# MainBoard.net
KiCad netlist of a schematic drawn in EAGLE
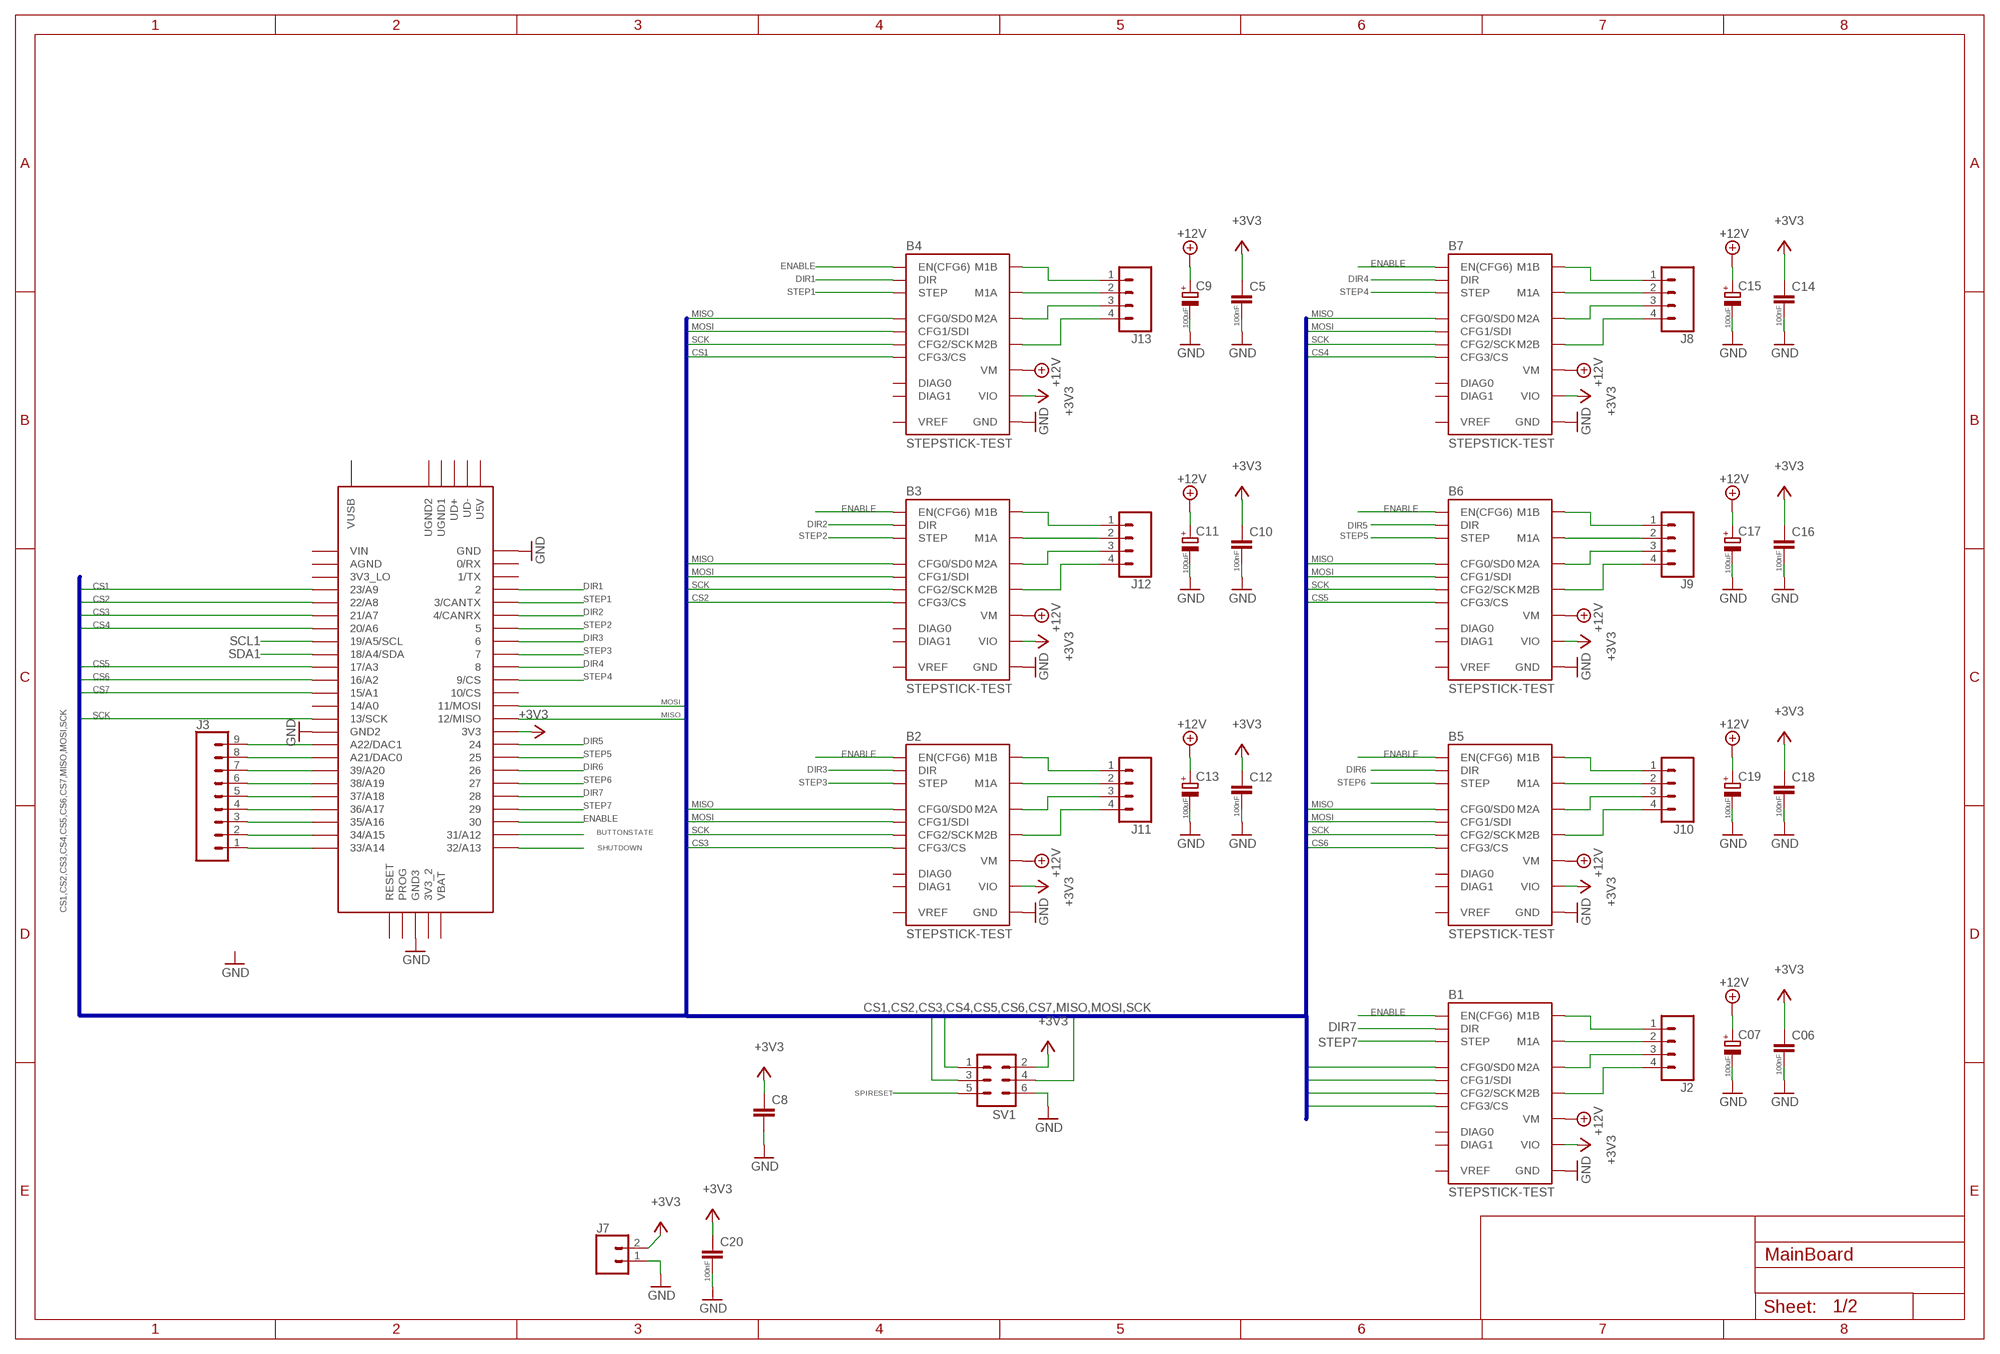
[diagram p0: schematic, sheet 1]
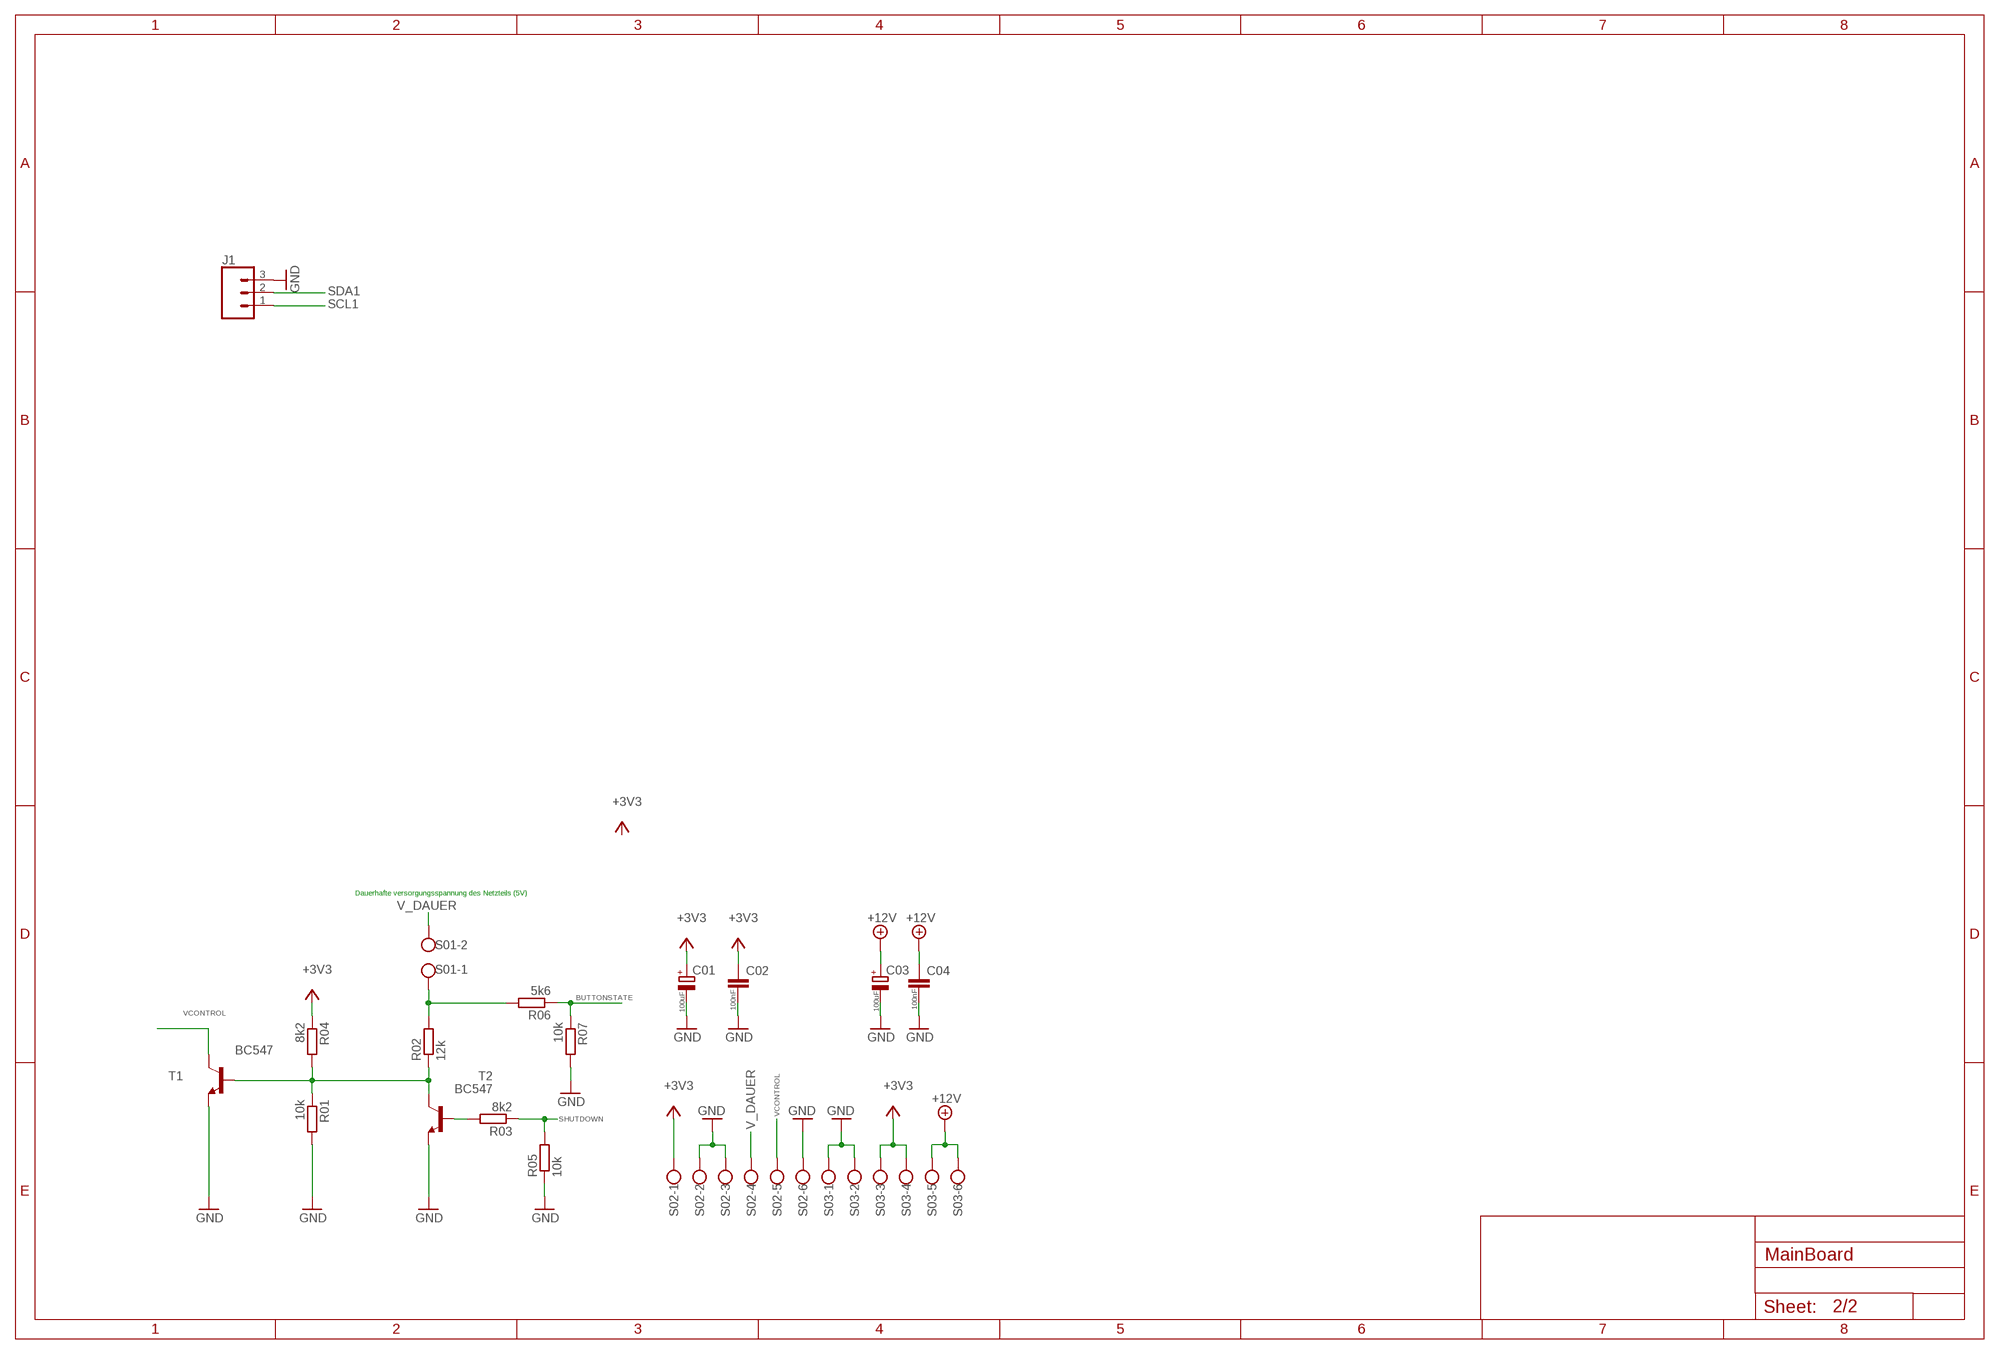
[diagram p1: schematic, sheet 2]

(export (version "E")
  (design (tool "Eeschema 10.0.6"))
  (components
    (comp (ref "C01")
      (value "100uF")
      (footprint "eagle-import:E2,5-6")
      (libsource (lib "eagle-import") (part "CPOL-EUE2.5-6"))
    )
    (comp (ref "C02")
      (value "100nF")
      (footprint "eagle-import:C050-024X044")
      (libsource (lib "eagle-import") (part "C-EU050-024X044"))
    )
    (comp (ref "C03")
      (value "100uF")
      (footprint "eagle-import:E2,5-6")
      (libsource (lib "eagle-import") (part "CPOL-EUE2.5-6"))
    )
    (comp (ref "C04")
      (value "100nF")
      (footprint "eagle-import:C050-024X044")
      (libsource (lib "eagle-import") (part "C-EU050-024X044"))
    )
    (comp (ref "J1")
      (value "CONN_03LONGPADS")
      (footprint "eagle-import:1X03_LONGPADS")
      (libsource (lib "eagle-import") (part "CONN_03LONGPADS"))
    )
    (comp (ref "R01")
      (value "10k")
      (footprint "eagle-import:0207_10")
      (libsource (lib "eagle-import") (part "R-EU_0207/10"))
    )
    (comp (ref "R02")
      (value "12k")
      (footprint "eagle-import:0207_10")
      (libsource (lib "eagle-import") (part "R-EU_0207/10"))
    )
    (comp (ref "R03")
      (value "8k2")
      (footprint "eagle-import:0207_10")
      (libsource (lib "eagle-import") (part "R-EU_0207/10"))
    )
    (comp (ref "R04")
      (value "8k2")
      (footprint "eagle-import:0207_10")
      (libsource (lib "eagle-import") (part "R-EU_0207/10"))
    )
    (comp (ref "R05")
      (value "10k")
      (footprint "eagle-import:0207_10")
      (libsource (lib "eagle-import") (part "R-EU_0207/10"))
    )
    (comp (ref "R06")
      (value "5k6")
      (footprint "eagle-import:0207_10")
      (libsource (lib "eagle-import") (part "R-EU_0207/10"))
    )
    (comp (ref "R07")
      (value "10k")
      (footprint "eagle-import:0207_10")
      (libsource (lib "eagle-import") (part "R-EU_0207/10"))
    )
    (comp (ref "S01")
      (value "W237-102")
      (footprint "eagle-import:W237-102")
      (fields (field (name "MPN") "237-102"))
      (libsource (lib "eagle-import") (part "W237-102"))
    )
    (comp (ref "S02")
      (value "W237-6")
      (footprint "eagle-import:W237-6")
      (libsource (lib "eagle-import") (part "W237-6"))
    )
    (comp (ref "S03")
      (value "W237-6")
      (footprint "eagle-import:W237-6")
      (libsource (lib "eagle-import") (part "W237-6"))
    )
    (comp (ref "T1")
      (value "BC547")
      (footprint "eagle-import:TO92")
      (libsource (lib "eagle-import") (part "BC547"))
    )
    (comp (ref "T2")
      (value "BC547")
      (footprint "eagle-import:TO92")
      (libsource (lib "eagle-import") (part "BC547"))
    )
    (comp (ref "B1")
      (value "STEPSTICK-TEST")
      (footprint "eagle-import:STEPSTICK-TEST")
      (libsource (lib "eagle-import") (part "STEPSTICK-TEST"))
    )
    (comp (ref "B2")
      (value "STEPSTICK-TEST")
      (footprint "eagle-import:STEPSTICK-TEST")
      (libsource (lib "eagle-import") (part "STEPSTICK-TEST"))
    )
    (comp (ref "B3")
      (value "STEPSTICK-TEST")
      (footprint "eagle-import:STEPSTICK-TEST")
      (libsource (lib "eagle-import") (part "STEPSTICK-TEST"))
    )
    (comp (ref "B4")
      (value "STEPSTICK-TEST")
      (footprint "eagle-import:STEPSTICK-TEST")
      (libsource (lib "eagle-import") (part "STEPSTICK-TEST"))
    )
    (comp (ref "B5")
      (value "STEPSTICK-TEST")
      (footprint "eagle-import:STEPSTICK-TEST")
      (libsource (lib "eagle-import") (part "STEPSTICK-TEST"))
    )
    (comp (ref "B6")
      (value "STEPSTICK-TEST")
      (footprint "eagle-import:STEPSTICK-TEST")
      (libsource (lib "eagle-import") (part "STEPSTICK-TEST"))
    )
    (comp (ref "B7")
      (value "STEPSTICK-TEST")
      (footprint "eagle-import:STEPSTICK-TEST")
      (libsource (lib "eagle-import") (part "STEPSTICK-TEST"))
    )
    (comp (ref "C5")
      (value "100nF")
      (footprint "eagle-import:C050-024X044")
      (libsource (lib "eagle-import") (part "C-EU050-024X044"))
    )
    (comp (ref "C06")
      (value "100nF")
      (footprint "eagle-import:C050-024X044")
      (libsource (lib "eagle-import") (part "C-EU050-024X044"))
    )
    (comp (ref "C07")
      (value "100uF")
      (footprint "eagle-import:E2,5-6")
      (libsource (lib "eagle-import") (part "CPOL-EUE2.5-6"))
    )
    (comp (ref "C8")
      (value "C-EU050-024X044")
      (footprint "eagle-import:C050-024X044")
      (libsource (lib "eagle-import") (part "C-EU050-024X044"))
    )
    (comp (ref "C9")
      (value "100uF")
      (footprint "eagle-import:E2,5-6")
      (libsource (lib "eagle-import") (part "CPOL-EUE2.5-6"))
    )
    (comp (ref "C10")
      (value "100nF")
      (footprint "eagle-import:C050-024X044")
      (libsource (lib "eagle-import") (part "C-EU050-024X044"))
    )
    (comp (ref "C11")
      (value "100uF")
      (footprint "eagle-import:E2,5-6")
      (libsource (lib "eagle-import") (part "CPOL-EUE2.5-6"))
    )
    (comp (ref "C12")
      (value "100nF")
      (footprint "eagle-import:C050-024X044")
      (libsource (lib "eagle-import") (part "C-EU050-024X044"))
    )
    (comp (ref "C13")
      (value "100uF")
      (footprint "eagle-import:E2,5-6")
      (libsource (lib "eagle-import") (part "CPOL-EUE2.5-6"))
    )
    (comp (ref "C14")
      (value "100nF")
      (footprint "eagle-import:C050-024X044")
      (libsource (lib "eagle-import") (part "C-EU050-024X044"))
    )
    (comp (ref "C15")
      (value "100uF")
      (footprint "eagle-import:E2,5-6")
      (libsource (lib "eagle-import") (part "CPOL-EUE2.5-6"))
    )
    (comp (ref "C16")
      (value "100nF")
      (footprint "eagle-import:C050-024X044")
      (libsource (lib "eagle-import") (part "C-EU050-024X044"))
    )
    (comp (ref "C17")
      (value "100uF")
      (footprint "eagle-import:E2,5-6")
      (libsource (lib "eagle-import") (part "CPOL-EUE2.5-6"))
    )
    (comp (ref "C18")
      (value "100nF")
      (footprint "eagle-import:C050-024X044")
      (libsource (lib "eagle-import") (part "C-EU050-024X044"))
    )
    (comp (ref "C19")
      (value "100uF")
      (footprint "eagle-import:E2,5-6")
      (libsource (lib "eagle-import") (part "CPOL-EUE2.5-6"))
    )
    (comp (ref "C20")
      (value "100nF")
      (footprint "eagle-import:C050-024X044")
      (libsource (lib "eagle-import") (part "C-EU050-024X044"))
    )
    (comp (ref "J2")
      (value "CONN_041X04_NO_SILK")
      (footprint "eagle-import:1X04_NO_SILK")
      (libsource (lib "eagle-import") (part "CONN_041X04_NO_SILK"))
    )
    (comp (ref "J3")
      (value "CONN_09LONGPADS")
      (footprint "eagle-import:1X09_LONGPADS")
      (libsource (lib "eagle-import") (part "CONN_09LONGPADS"))
    )
    (comp (ref "J7")
      (value "CONN_02PTH3")
      (footprint "eagle-import:1X02_LONGPADS")
      (libsource (lib "eagle-import") (part "CONN_02PTH3"))
    )
    (comp (ref "J8")
      (value "CONN_041X04_NO_SILK")
      (footprint "eagle-import:1X04_NO_SILK")
      (libsource (lib "eagle-import") (part "CONN_041X04_NO_SILK"))
    )
    (comp (ref "J9")
      (value "CONN_041X04_NO_SILK")
      (footprint "eagle-import:1X04_NO_SILK")
      (libsource (lib "eagle-import") (part "CONN_041X04_NO_SILK"))
    )
    (comp (ref "J10")
      (value "CONN_041X04_NO_SILK")
      (footprint "eagle-import:1X04_NO_SILK")
      (libsource (lib "eagle-import") (part "CONN_041X04_NO_SILK"))
    )
    (comp (ref "J11")
      (value "CONN_041X04_NO_SILK")
      (footprint "eagle-import:1X04_NO_SILK")
      (libsource (lib "eagle-import") (part "CONN_041X04_NO_SILK"))
    )
    (comp (ref "J12")
      (value "CONN_041X04_NO_SILK")
      (footprint "eagle-import:1X04_NO_SILK")
      (libsource (lib "eagle-import") (part "CONN_041X04_NO_SILK"))
    )
    (comp (ref "J13")
      (value "CONN_041X04_NO_SILK")
      (footprint "eagle-import:1X04_NO_SILK")
      (libsource (lib "eagle-import") (part "CONN_041X04_NO_SILK"))
    )
    (comp (ref "SV1")
      (value "MA03-2")
      (footprint "eagle-import:MA03-2")
      (libsource (lib "eagle-import") (part "MA03-2"))
    )
    (comp (ref "U$1")
      (value "TEENSY_4.1")
      (footprint "eagle-import:TEENSY_4.1")
      (libsource (lib "eagle-import") (part "TEENSY_4.1"))
    )
  )
  (nets
    (net (code "1") (name "+3V3") (class "Default")
      (node (ref "B1") (pin "VIO") (pinfunction "VIO_VIO") (pintype "power_in"))
      (node (ref "B2") (pin "VIO") (pinfunction "VIO_VIO") (pintype "power_in"))
      (node (ref "B3") (pin "VIO") (pinfunction "VIO_VIO") (pintype "power_in"))
      (node (ref "B4") (pin "VIO") (pinfunction "VIO_VIO") (pintype "power_in"))
      (node (ref "B5") (pin "VIO") (pinfunction "VIO_VIO") (pintype "power_in"))
      (node (ref "B6") (pin "VIO") (pinfunction "VIO_VIO") (pintype "power_in"))
      (node (ref "B7") (pin "VIO") (pinfunction "VIO_VIO") (pintype "power_in"))
      (node (ref "C01") (pin "+") (pinfunction "+_+") (pintype "passive"))
      (node (ref "C02") (pin "1") (pinfunction "1_1") (pintype "passive"))
      (node (ref "C06") (pin "1") (pinfunction "1_1") (pintype "passive"))
      (node (ref "C10") (pin "1") (pinfunction "1_1") (pintype "passive"))
      (node (ref "C12") (pin "1") (pinfunction "1_1") (pintype "passive"))
      (node (ref "C14") (pin "1") (pinfunction "1_1") (pintype "passive"))
      (node (ref "C16") (pin "1") (pinfunction "1_1") (pintype "passive"))
      (node (ref "C18") (pin "1") (pinfunction "1_1") (pintype "passive"))
      (node (ref "C20") (pin "1") (pinfunction "1_1") (pintype "passive"))
      (node (ref "C5") (pin "1") (pinfunction "1_1") (pintype "passive"))
      (node (ref "C8") (pin "1") (pinfunction "1_1") (pintype "passive"))
      (node (ref "J7") (pin "2") (pinfunction "2_2") (pintype "passive"))
      (node (ref "R04") (pin "1") (pinfunction "1_1") (pintype "passive"))
      (node (ref "S02") (pin "1") (pinfunction "KL_1") (pintype "passive"))
      (node (ref "S03") (pin "3") (pinfunction "KL_3") (pintype "passive"))
      (node (ref "S03") (pin "4") (pinfunction "KL_4") (pintype "passive"))
      (node (ref "SV1") (pin "2") (pinfunction "2_2") (pintype "passive"))
      (node (ref "U$1") (pin "3V3") (pinfunction "3V3_3V3") (pintype "bidirectional"))
    )
    (net (code "2") (name "+12V") (class "Default")
      (node (ref "B1") (pin "VM") (pinfunction "VM_VM") (pintype "power_in"))
      (node (ref "B2") (pin "VM") (pinfunction "VM_VM") (pintype "power_in"))
      (node (ref "B3") (pin "VM") (pinfunction "VM_VM") (pintype "power_in"))
      (node (ref "B4") (pin "VM") (pinfunction "VM_VM") (pintype "power_in"))
      (node (ref "B5") (pin "VM") (pinfunction "VM_VM") (pintype "power_in"))
      (node (ref "B6") (pin "VM") (pinfunction "VM_VM") (pintype "power_in"))
      (node (ref "B7") (pin "VM") (pinfunction "VM_VM") (pintype "power_in"))
      (node (ref "C03") (pin "+") (pinfunction "+_+") (pintype "passive"))
      (node (ref "C04") (pin "1") (pinfunction "1_1") (pintype "passive"))
      (node (ref "C07") (pin "+") (pinfunction "+_+") (pintype "passive"))
      (node (ref "C11") (pin "+") (pinfunction "+_+") (pintype "passive"))
      (node (ref "C13") (pin "+") (pinfunction "+_+") (pintype "passive"))
      (node (ref "C15") (pin "+") (pinfunction "+_+") (pintype "passive"))
      (node (ref "C17") (pin "+") (pinfunction "+_+") (pintype "passive"))
      (node (ref "C19") (pin "+") (pinfunction "+_+") (pintype "passive"))
      (node (ref "C9") (pin "+") (pinfunction "+_+") (pintype "passive"))
      (node (ref "S03") (pin "5") (pinfunction "KL_5") (pintype "passive"))
      (node (ref "S03") (pin "6") (pinfunction "KL_6") (pintype "passive"))
    )
    (net (code "4") (name "BUTTONSTATE") (class "Default")
      (node (ref "R06") (pin "1") (pinfunction "1_1") (pintype "passive"))
      (node (ref "R07") (pin "1") (pinfunction "1_1") (pintype "passive"))
      (node (ref "U$1") (pin "31/A12") (pinfunction "31/A12_31/A12") (pintype "bidirectional"))
    )
    (net (code "5") (name "CS1") (class "Default")
      (node (ref "B4") (pin "CFG3") (pinfunction "CFG3/CS_CFG3") (pintype "bidirectional"))
      (node (ref "U$1") (pin "23/A9") (pinfunction "23/A9_23/A9") (pintype "bidirectional"))
    )
    (net (code "6") (name "CS2") (class "Default")
      (node (ref "B3") (pin "CFG3") (pinfunction "CFG3/CS_CFG3") (pintype "bidirectional"))
      (node (ref "U$1") (pin "22/A8") (pinfunction "22/A8_22/A8") (pintype "bidirectional"))
    )
    (net (code "7") (name "CS3") (class "Default")
      (node (ref "B2") (pin "CFG3") (pinfunction "CFG3/CS_CFG3") (pintype "bidirectional"))
      (node (ref "U$1") (pin "21/A7") (pinfunction "21/A7_21/A7") (pintype "bidirectional"))
    )
    (net (code "8") (name "CS4") (class "Default")
      (node (ref "B7") (pin "CFG3") (pinfunction "CFG3/CS_CFG3") (pintype "bidirectional"))
      (node (ref "U$1") (pin "20/A6") (pinfunction "20/A6_20/A6") (pintype "bidirectional"))
    )
    (net (code "9") (name "CS5") (class "Default")
      (node (ref "B6") (pin "CFG3") (pinfunction "CFG3/CS_CFG3") (pintype "bidirectional"))
      (node (ref "U$1") (pin "17/A3") (pinfunction "17/A3_17/A3") (pintype "bidirectional"))
    )
    (net (code "10") (name "CS6") (class "Default")
      (node (ref "B5") (pin "CFG3") (pinfunction "CFG3/CS_CFG3") (pintype "bidirectional"))
      (node (ref "U$1") (pin "16/A2") (pinfunction "16/A2_16/A2") (pintype "bidirectional"))
    )
    (net (code "11") (name "CS7") (class "Default")
      (node (ref "B1") (pin "CFG3") (pinfunction "CFG3/CS_CFG3") (pintype "bidirectional"))
      (node (ref "U$1") (pin "15/A1") (pinfunction "15/A1_15/A1") (pintype "bidirectional"))
    )
    (net (code "12") (name "DIR1") (class "Default")
      (node (ref "B4") (pin "DIR") (pinfunction "DIR_DIR") (pintype "bidirectional"))
      (node (ref "U$1") (pin "2") (pinfunction "2_2") (pintype "bidirectional"))
    )
    (net (code "13") (name "DIR2") (class "Default")
      (node (ref "B3") (pin "DIR") (pinfunction "DIR_DIR") (pintype "bidirectional"))
      (node (ref "U$1") (pin "4/CANRX") (pinfunction "4/CANRX_4/CANRX") (pintype "bidirectional"))
    )
    (net (code "14") (name "DIR3") (class "Default")
      (node (ref "B2") (pin "DIR") (pinfunction "DIR_DIR") (pintype "bidirectional"))
      (node (ref "U$1") (pin "6") (pinfunction "6_6") (pintype "bidirectional"))
    )
    (net (code "15") (name "DIR4") (class "Default")
      (node (ref "B7") (pin "DIR") (pinfunction "DIR_DIR") (pintype "bidirectional"))
      (node (ref "U$1") (pin "8") (pinfunction "8_8") (pintype "bidirectional"))
    )
    (net (code "16") (name "DIR5") (class "Default")
      (node (ref "B6") (pin "DIR") (pinfunction "DIR_DIR") (pintype "bidirectional"))
      (node (ref "U$1") (pin "24/A10") (pinfunction "24_24/A10") (pintype "bidirectional"))
    )
    (net (code "17") (name "DIR6") (class "Default")
      (node (ref "B5") (pin "DIR") (pinfunction "DIR_DIR") (pintype "bidirectional"))
      (node (ref "U$1") (pin "26/12") (pinfunction "26_26/12") (pintype "bidirectional"))
    )
    (net (code "18") (name "DIR7") (class "Default")
      (node (ref "B1") (pin "DIR") (pinfunction "DIR_DIR") (pintype "bidirectional"))
      (node (ref "U$1") (pin "28") (pinfunction "28_28") (pintype "bidirectional"))
    )
    (net (code "19") (name "ENABLE") (class "Default")
      (node (ref "B1") (pin "EN") (pinfunction "EN(CFG6)_EN") (pintype "bidirectional"))
      (node (ref "B2") (pin "EN") (pinfunction "EN(CFG6)_EN") (pintype "bidirectional"))
      (node (ref "B3") (pin "EN") (pinfunction "EN(CFG6)_EN") (pintype "bidirectional"))
      (node (ref "B4") (pin "EN") (pinfunction "EN(CFG6)_EN") (pintype "bidirectional"))
      (node (ref "B5") (pin "EN") (pinfunction "EN(CFG6)_EN") (pintype "bidirectional"))
      (node (ref "B6") (pin "EN") (pinfunction "EN(CFG6)_EN") (pintype "bidirectional"))
      (node (ref "B7") (pin "EN") (pinfunction "EN(CFG6)_EN") (pintype "bidirectional"))
      (node (ref "U$1") (pin "30") (pinfunction "30_30") (pintype "bidirectional"))
    )
    (net (code "20") (name "GND") (class "Default")
      (node (ref "B1") (pin "GND@1") (pinfunction "GND_GND@1") (pintype "power_in"))
      (node (ref "B1") (pin "GND@2") (pinfunction "GND_GND@2") (pintype "power_in"))
      (node (ref "B2") (pin "GND@1") (pinfunction "GND_GND@1") (pintype "power_in"))
      (node (ref "B2") (pin "GND@2") (pinfunction "GND_GND@2") (pintype "power_in"))
      (node (ref "B3") (pin "GND@1") (pinfunction "GND_GND@1") (pintype "power_in"))
      (node (ref "B3") (pin "GND@2") (pinfunction "GND_GND@2") (pintype "power_in"))
      (node (ref "B4") (pin "GND@1") (pinfunction "GND_GND@1") (pintype "power_in"))
      (node (ref "B4") (pin "GND@2") (pinfunction "GND_GND@2") (pintype "power_in"))
      (node (ref "B5") (pin "GND@1") (pinfunction "GND_GND@1") (pintype "power_in"))
      (node (ref "B5") (pin "GND@2") (pinfunction "GND_GND@2") (pintype "power_in"))
      (node (ref "B6") (pin "GND@1") (pinfunction "GND_GND@1") (pintype "power_in"))
      (node (ref "B6") (pin "GND@2") (pinfunction "GND_GND@2") (pintype "power_in"))
      (node (ref "B7") (pin "GND@1") (pinfunction "GND_GND@1") (pintype "power_in"))
      (node (ref "B7") (pin "GND@2") (pinfunction "GND_GND@2") (pintype "power_in"))
      (node (ref "C01") (pin "-") (pinfunction "-_-") (pintype "passive"))
      (node (ref "C02") (pin "2") (pinfunction "2_2") (pintype "passive"))
      (node (ref "C03") (pin "-") (pinfunction "-_-") (pintype "passive"))
      (node (ref "C04") (pin "2") (pinfunction "2_2") (pintype "passive"))
      (node (ref "C06") (pin "2") (pinfunction "2_2") (pintype "passive"))
      (node (ref "C07") (pin "-") (pinfunction "-_-") (pintype "passive"))
      (node (ref "C10") (pin "2") (pinfunction "2_2") (pintype "passive"))
      (node (ref "C11") (pin "-") (pinfunction "-_-") (pintype "passive"))
      (node (ref "C12") (pin "2") (pinfunction "2_2") (pintype "passive"))
      (node (ref "C13") (pin "-") (pinfunction "-_-") (pintype "passive"))
      (node (ref "C14") (pin "2") (pinfunction "2_2") (pintype "passive"))
      (node (ref "C15") (pin "-") (pinfunction "-_-") (pintype "passive"))
      (node (ref "C16") (pin "2") (pinfunction "2_2") (pintype "passive"))
      (node (ref "C17") (pin "-") (pinfunction "-_-") (pintype "passive"))
      (node (ref "C18") (pin "2") (pinfunction "2_2") (pintype "passive"))
      (node (ref "C19") (pin "-") (pinfunction "-_-") (pintype "passive"))
      (node (ref "C20") (pin "2") (pinfunction "2_2") (pintype "passive"))
      (node (ref "C5") (pin "2") (pinfunction "2_2") (pintype "passive"))
      (node (ref "C8") (pin "2") (pinfunction "2_2") (pintype "passive"))
      (node (ref "C9") (pin "-") (pinfunction "-_-") (pintype "passive"))
      (node (ref "J1") (pin "3") (pinfunction "3_3") (pintype "passive"))
      (node (ref "J7") (pin "1") (pinfunction "1_1") (pintype "passive"))
      (node (ref "R01") (pin "2") (pinfunction "2_2") (pintype "passive"))
      (node (ref "R05") (pin "1") (pinfunction "1_1") (pintype "passive"))
      (node (ref "R07") (pin "2") (pinfunction "2_2") (pintype "passive"))
      (node (ref "S02") (pin "2") (pinfunction "KL_2") (pintype "passive"))
      (node (ref "S02") (pin "3") (pinfunction "KL_3") (pintype "passive"))
      (node (ref "S02") (pin "6") (pinfunction "KL_6") (pintype "passive"))
      (node (ref "S03") (pin "1") (pinfunction "KL_1") (pintype "passive"))
      (node (ref "S03") (pin "2") (pinfunction "KL_2") (pintype "passive"))
      (node (ref "SV1") (pin "6") (pinfunction "6_6") (pintype "passive"))
      (node (ref "T1") (pin "1") (pinfunction "E_1") (pintype "passive"))
      (node (ref "T2") (pin "1") (pinfunction "E_1") (pintype "passive"))
      (node (ref "U$1") (pin "GND") (pinfunction "GND_GND") (pintype "bidirectional"))
      (node (ref "U$1") (pin "GND2") (pinfunction "GND2_GND2") (pintype "bidirectional"))
      (node (ref "U$1") (pin "GND3") (pinfunction "GND3_GND3") (pintype "bidirectional"))
    )
    (net (code "21") (name "MISO") (class "Default")
      (node (ref "B1") (pin "NC/CFG0") (pinfunction "CFG0/SD0_NC/CFG0") (pintype "bidirectional"))
      (node (ref "B2") (pin "NC/CFG0") (pinfunction "CFG0/SD0_NC/CFG0") (pintype "bidirectional"))
      (node (ref "B3") (pin "NC/CFG0") (pinfunction "CFG0/SD0_NC/CFG0") (pintype "bidirectional"))
      (node (ref "B4") (pin "NC/CFG0") (pinfunction "CFG0/SD0_NC/CFG0") (pintype "bidirectional"))
      (node (ref "B5") (pin "NC/CFG0") (pinfunction "CFG0/SD0_NC/CFG0") (pintype "bidirectional"))
      (node (ref "B6") (pin "NC/CFG0") (pinfunction "CFG0/SD0_NC/CFG0") (pintype "bidirectional"))
      (node (ref "B7") (pin "NC/CFG0") (pinfunction "CFG0/SD0_NC/CFG0") (pintype "bidirectional"))
      (node (ref "SV1") (pin "1") (pinfunction "1_1") (pintype "passive"))
      (node (ref "U$1") (pin "12/MISO") (pinfunction "12/MISO_12/MISO") (pintype "bidirectional"))
    )
    (net (code "22") (name "MOSI") (class "Default")
      (node (ref "B1") (pin "CFG1") (pinfunction "CFG1/SDI_CFG1") (pintype "bidirectional"))
      (node (ref "B2") (pin "CFG1") (pinfunction "CFG1/SDI_CFG1") (pintype "bidirectional"))
      (node (ref "B3") (pin "CFG1") (pinfunction "CFG1/SDI_CFG1") (pintype "bidirectional"))
      (node (ref "B4") (pin "CFG1") (pinfunction "CFG1/SDI_CFG1") (pintype "bidirectional"))
      (node (ref "B5") (pin "CFG1") (pinfunction "CFG1/SDI_CFG1") (pintype "bidirectional"))
      (node (ref "B6") (pin "CFG1") (pinfunction "CFG1/SDI_CFG1") (pintype "bidirectional"))
      (node (ref "B7") (pin "CFG1") (pinfunction "CFG1/SDI_CFG1") (pintype "bidirectional"))
      (node (ref "SV1") (pin "4") (pinfunction "4_4") (pintype "passive"))
      (node (ref "U$1") (pin "11/MOSI") (pinfunction "11/MOSI_11/MOSI") (pintype "bidirectional"))
    )
    (net (code "23") (name "Net-(B1-PadM1A)") (class "Default")
      (node (ref "B1") (pin "M1A") (pinfunction "M1A_M1A") (pintype "output"))
      (node (ref "J2") (pin "2") (pinfunction "2_2") (pintype "passive"))
    )
    (net (code "24") (name "Net-(B1-PadM1B)") (class "Default")
      (node (ref "B1") (pin "M1B") (pinfunction "M1B_M1B") (pintype "output"))
      (node (ref "J2") (pin "1") (pinfunction "1_1") (pintype "passive"))
    )
    (net (code "25") (name "Net-(B1-PadM2A)") (class "Default")
      (node (ref "B1") (pin "M2A") (pinfunction "M2A_M2A") (pintype "output"))
      (node (ref "J2") (pin "3") (pinfunction "3_3") (pintype "passive"))
    )
    (net (code "26") (name "Net-(B1-PadM2B)") (class "Default")
      (node (ref "B1") (pin "M2B") (pinfunction "M2B_M2B") (pintype "output"))
      (node (ref "J2") (pin "4") (pinfunction "4_4") (pintype "passive"))
    )
    (net (code "27") (name "Net-(B2-PadM1A)") (class "Default")
      (node (ref "B2") (pin "M1A") (pinfunction "M1A_M1A") (pintype "output"))
      (node (ref "J11") (pin "2") (pinfunction "2_2") (pintype "passive"))
    )
    (net (code "28") (name "Net-(B2-PadM1B)") (class "Default")
      (node (ref "B2") (pin "M1B") (pinfunction "M1B_M1B") (pintype "output"))
      (node (ref "J11") (pin "1") (pinfunction "1_1") (pintype "passive"))
    )
    (net (code "29") (name "Net-(B2-PadM2A)") (class "Default")
      (node (ref "B2") (pin "M2A") (pinfunction "M2A_M2A") (pintype "output"))
      (node (ref "J11") (pin "3") (pinfunction "3_3") (pintype "passive"))
    )
    (net (code "30") (name "Net-(B2-PadM2B)") (class "Default")
      (node (ref "B2") (pin "M2B") (pinfunction "M2B_M2B") (pintype "output"))
      (node (ref "J11") (pin "4") (pinfunction "4_4") (pintype "passive"))
    )
    (net (code "31") (name "Net-(B3-PadM1A)") (class "Default")
      (node (ref "B3") (pin "M1A") (pinfunction "M1A_M1A") (pintype "output"))
      (node (ref "J12") (pin "2") (pinfunction "2_2") (pintype "passive"))
    )
    (net (code "32") (name "Net-(B3-PadM1B)") (class "Default")
      (node (ref "B3") (pin "M1B") (pinfunction "M1B_M1B") (pintype "output"))
      (node (ref "J12") (pin "1") (pinfunction "1_1") (pintype "passive"))
    )
    (net (code "33") (name "Net-(B3-PadM2A)") (class "Default")
      (node (ref "B3") (pin "M2A") (pinfunction "M2A_M2A") (pintype "output"))
      (node (ref "J12") (pin "3") (pinfunction "3_3") (pintype "passive"))
    )
    (net (code "34") (name "Net-(B3-PadM2B)") (class "Default")
      (node (ref "B3") (pin "M2B") (pinfunction "M2B_M2B") (pintype "output"))
      (node (ref "J12") (pin "4") (pinfunction "4_4") (pintype "passive"))
    )
    (net (code "35") (name "Net-(B4-PadM1A)") (class "Default")
      (node (ref "B4") (pin "M1A") (pinfunction "M1A_M1A") (pintype "output"))
      (node (ref "J13") (pin "2") (pinfunction "2_2") (pintype "passive"))
    )
    (net (code "36") (name "Net-(B4-PadM1B)") (class "Default")
      (node (ref "B4") (pin "M1B") (pinfunction "M1B_M1B") (pintype "output"))
      (node (ref "J13") (pin "1") (pinfunction "1_1") (pintype "passive"))
    )
    (net (code "37") (name "Net-(B4-PadM2A)") (class "Default")
      (node (ref "B4") (pin "M2A") (pinfunction "M2A_M2A") (pintype "output"))
      (node (ref "J13") (pin "3") (pinfunction "3_3") (pintype "passive"))
    )
    (net (code "38") (name "Net-(B4-PadM2B)") (class "Default")
      (node (ref "B4") (pin "M2B") (pinfunction "M2B_M2B") (pintype "output"))
      (node (ref "J13") (pin "4") (pinfunction "4_4") (pintype "passive"))
    )
    (net (code "39") (name "Net-(B5-PadM1A)") (class "Default")
      (node (ref "B5") (pin "M1A") (pinfunction "M1A_M1A") (pintype "output"))
      (node (ref "J10") (pin "2") (pinfunction "2_2") (pintype "passive"))
    )
    (net (code "40") (name "Net-(B5-PadM1B)") (class "Default")
      (node (ref "B5") (pin "M1B") (pinfunction "M1B_M1B") (pintype "output"))
      (node (ref "J10") (pin "1") (pinfunction "1_1") (pintype "passive"))
    )
    (net (code "41") (name "Net-(B5-PadM2A)") (class "Default")
      (node (ref "B5") (pin "M2A") (pinfunction "M2A_M2A") (pintype "output"))
      (node (ref "J10") (pin "3") (pinfunction "3_3") (pintype "passive"))
    )
    (net (code "42") (name "Net-(B5-PadM2B)") (class "Default")
      (node (ref "B5") (pin "M2B") (pinfunction "M2B_M2B") (pintype "output"))
      (node (ref "J10") (pin "4") (pinfunction "4_4") (pintype "passive"))
    )
    (net (code "43") (name "Net-(B6-PadM1A)") (class "Default")
      (node (ref "B6") (pin "M1A") (pinfunction "M1A_M1A") (pintype "output"))
      (node (ref "J9") (pin "2") (pinfunction "2_2") (pintype "passive"))
    )
    (net (code "44") (name "Net-(B6-PadM1B)") (class "Default")
      (node (ref "B6") (pin "M1B") (pinfunction "M1B_M1B") (pintype "output"))
      (node (ref "J9") (pin "1") (pinfunction "1_1") (pintype "passive"))
    )
    (net (code "45") (name "Net-(B6-PadM2A)") (class "Default")
      (node (ref "B6") (pin "M2A") (pinfunction "M2A_M2A") (pintype "output"))
      (node (ref "J9") (pin "3") (pinfunction "3_3") (pintype "passive"))
    )
    (net (code "46") (name "Net-(B6-PadM2B)") (class "Default")
      (node (ref "B6") (pin "M2B") (pinfunction "M2B_M2B") (pintype "output"))
      (node (ref "J9") (pin "4") (pinfunction "4_4") (pintype "passive"))
    )
    (net (code "47") (name "Net-(B7-PadM1A)") (class "Default")
      (node (ref "B7") (pin "M1A") (pinfunction "M1A_M1A") (pintype "output"))
      (node (ref "J8") (pin "2") (pinfunction "2_2") (pintype "passive"))
    )
    (net (code "48") (name "Net-(B7-PadM1B)") (class "Default")
      (node (ref "B7") (pin "M1B") (pinfunction "M1B_M1B") (pintype "output"))
      (node (ref "J8") (pin "1") (pinfunction "1_1") (pintype "passive"))
    )
    (net (code "49") (name "Net-(B7-PadM2A)") (class "Default")
      (node (ref "B7") (pin "M2A") (pinfunction "M2A_M2A") (pintype "output"))
      (node (ref "J8") (pin "3") (pinfunction "3_3") (pintype "passive"))
    )
    (net (code "50") (name "Net-(B7-PadM2B)") (class "Default")
      (node (ref "B7") (pin "M2B") (pinfunction "M2B_M2B") (pintype "output"))
      (node (ref "J8") (pin "4") (pinfunction "4_4") (pintype "passive"))
    )
    (net (code "51") (name "Net-(J3-Pad1)") (class "Default")
      (node (ref "J3") (pin "1") (pinfunction "1_1") (pintype "passive"))
      (node (ref "U$1") (pin "33/A14") (pinfunction "33/A14_33/A14") (pintype "bidirectional"))
    )
    (net (code "52") (name "Net-(J3-Pad2)") (class "Default")
      (node (ref "J3") (pin "2") (pinfunction "2_2") (pintype "passive"))
      (node (ref "U$1") (pin "34/A15") (pinfunction "34/A15_34/A15") (pintype "bidirectional"))
    )
    (net (code "53") (name "Net-(J3-Pad3)") (class "Default")
      (node (ref "J3") (pin "3") (pinfunction "3_3") (pintype "passive"))
      (node (ref "U$1") (pin "35/A16") (pinfunction "35/A16_35/A16") (pintype "bidirectional"))
    )
    (net (code "54") (name "Net-(J3-Pad4)") (class "Default")
      (node (ref "J3") (pin "4") (pinfunction "4_4") (pintype "passive"))
      (node (ref "U$1") (pin "36/A17") (pinfunction "36/A17_36/A17") (pintype "bidirectional"))
    )
    (net (code "55") (name "Net-(J3-Pad5)") (class "Default")
      (node (ref "J3") (pin "5") (pinfunction "5_5") (pintype "passive"))
      (node (ref "U$1") (pin "37/A18") (pinfunction "37/A18_37/A18") (pintype "bidirectional"))
    )
    (net (code "56") (name "Net-(J3-Pad6)") (class "Default")
      (node (ref "J3") (pin "6") (pinfunction "6_6") (pintype "passive"))
      (node (ref "U$1") (pin "38/A19") (pinfunction "38/A19_38/A19") (pintype "bidirectional"))
    )
    (net (code "57") (name "Net-(J3-Pad7)") (class "Default")
      (node (ref "J3") (pin "7") (pinfunction "7_7") (pintype "passive"))
      (node (ref "U$1") (pin "39/A20") (pinfunction "39/A20_39/A20") (pintype "bidirectional"))
    )
    (net (code "58") (name "Net-(J3-Pad9)") (class "Default")
      (node (ref "J3") (pin "9") (pinfunction "9_9") (pintype "passive"))
      (node (ref "U$1") (pin "A22/DAC1") (pinfunction "A22/DAC1_A22/DAC1") (pintype "bidirectional"))
    )
    (net (code "59") (name "Net-(S01A-KL)") (class "Default")
      (node (ref "R02") (pin "2") (pinfunction "2_2") (pintype "passive"))
      (node (ref "R06") (pin "2") (pinfunction "2_2") (pintype "passive"))
      (node (ref "S01") (pin "1") (pinfunction "KL_1") (pintype "passive"))
    )
    (net (code "60") (name "Net-(T1-B)") (class "Default")
      (node (ref "R01") (pin "1") (pinfunction "1_1") (pintype "passive"))
      (node (ref "R02") (pin "1") (pinfunction "1_1") (pintype "passive"))
      (node (ref "R04") (pin "2") (pinfunction "2_2") (pintype "passive"))
      (node (ref "T1") (pin "2") (pinfunction "B_2") (pintype "passive"))
      (node (ref "T2") (pin "3") (pinfunction "C_3") (pintype "passive"))
    )
    (net (code "61") (name "Net-(T2-B)") (class "Default")
      (node (ref "R03") (pin "2") (pinfunction "2_2") (pintype "passive"))
      (node (ref "T2") (pin "2") (pinfunction "B_2") (pintype "passive"))
    )
    (net (code "62") (name "Net-(U$1-A21{slash}DAC0)") (class "Default")
      (node (ref "J3") (pin "8") (pinfunction "8_8") (pintype "passive"))
      (node (ref "U$1") (pin "21/DAC0") (pinfunction "A21/DAC0_21/DAC0") (pintype "bidirectional"))
    )
    (net (code "63") (name "SCK") (class "Default")
      (node (ref "B1") (pin "CFG2") (pinfunction "CFG2/SCK_CFG2") (pintype "bidirectional"))
      (node (ref "B2") (pin "CFG2") (pinfunction "CFG2/SCK_CFG2") (pintype "bidirectional"))
      (node (ref "B3") (pin "CFG2") (pinfunction "CFG2/SCK_CFG2") (pintype "bidirectional"))
      (node (ref "B4") (pin "CFG2") (pinfunction "CFG2/SCK_CFG2") (pintype "bidirectional"))
      (node (ref "B5") (pin "CFG2") (pinfunction "CFG2/SCK_CFG2") (pintype "bidirectional"))
      (node (ref "B6") (pin "CFG2") (pinfunction "CFG2/SCK_CFG2") (pintype "bidirectional"))
      (node (ref "B7") (pin "CFG2") (pinfunction "CFG2/SCK_CFG2") (pintype "bidirectional"))
      (node (ref "SV1") (pin "3") (pinfunction "3_3") (pintype "passive"))
      (node (ref "U$1") (pin "13/SCK") (pinfunction "13/SCK_13/SCK") (pintype "bidirectional"))
    )
    (net (code "64") (name "SCL1") (class "Default")
      (node (ref "J1") (pin "1") (pinfunction "1_1") (pintype "passive"))
      (node (ref "U$1") (pin "19/A5/SCL") (pinfunction "19/A5/SCL_19/A5/SCL") (pintype "bidirectional"))
    )
    (net (code "65") (name "SDA1") (class "Default")
      (node (ref "J1") (pin "2") (pinfunction "2_2") (pintype "passive"))
      (node (ref "U$1") (pin "18/A4/SDA") (pinfunction "18/A4/SDA_18/A4/SDA") (pintype "bidirectional"))
    )
    (net (code "66") (name "SHUTDOWN") (class "Default")
      (node (ref "R03") (pin "1") (pinfunction "1_1") (pintype "passive"))
      (node (ref "R05") (pin "2") (pinfunction "2_2") (pintype "passive"))
      (node (ref "U$1") (pin "32/A13") (pinfunction "32/A13_32/A13") (pintype "bidirectional"))
    )
    (net (code "67") (name "SPIRESET") (class "Default")
      (node (ref "SV1") (pin "5") (pinfunction "5_5") (pintype "passive"))
    )
    (net (code "68") (name "STEP1") (class "Default")
      (node (ref "B4") (pin "STEP") (pinfunction "STEP_STEP") (pintype "bidirectional"))
      (node (ref "U$1") (pin "3/CANTX") (pinfunction "3/CANTX_3/CANTX") (pintype "bidirectional"))
    )
    (net (code "69") (name "STEP2") (class "Default")
      (node (ref "B3") (pin "STEP") (pinfunction "STEP_STEP") (pintype "bidirectional"))
      (node (ref "U$1") (pin "5") (pinfunction "5_5") (pintype "bidirectional"))
    )
    (net (code "70") (name "STEP3") (class "Default")
      (node (ref "B2") (pin "STEP") (pinfunction "STEP_STEP") (pintype "bidirectional"))
      (node (ref "U$1") (pin "7") (pinfunction "7_7") (pintype "bidirectional"))
    )
    (net (code "71") (name "STEP4") (class "Default")
      (node (ref "B7") (pin "STEP") (pinfunction "STEP_STEP") (pintype "bidirectional"))
      (node (ref "U$1") (pin "9/CS") (pinfunction "9/CS_9/CS") (pintype "bidirectional"))
    )
    (net (code "72") (name "STEP5") (class "Default")
      (node (ref "B6") (pin "STEP") (pinfunction "STEP_STEP") (pintype "bidirectional"))
      (node (ref "U$1") (pin "25/A11") (pinfunction "25_25/A11") (pintype "bidirectional"))
    )
    (net (code "73") (name "STEP6") (class "Default")
      (node (ref "B5") (pin "STEP") (pinfunction "STEP_STEP") (pintype "bidirectional"))
      (node (ref "U$1") (pin "27/A13") (pinfunction "27_27/A13") (pintype "bidirectional"))
    )
    (net (code "74") (name "STEP7") (class "Default")
      (node (ref "B1") (pin "STEP") (pinfunction "STEP_STEP") (pintype "bidirectional"))
      (node (ref "U$1") (pin "29") (pinfunction "29_29") (pintype "bidirectional"))
    )
    (net (code "75") (name "VCONTROL") (class "Default")
      (node (ref "S02") (pin "5") (pinfunction "KL_5") (pintype "passive"))
      (node (ref "T1") (pin "3") (pinfunction "C_3") (pintype "passive"))
    )
    (net (code "76") (name "V_DAUER") (class "Default")
      (node (ref "S01") (pin "2") (pinfunction "KL_2") (pintype "passive"))
      (node (ref "S02") (pin "4") (pinfunction "KL_4") (pintype "passive"))
    )
    (net (code "77") (name "unconnected-(B1-PadDIAG0)") (class "Default")
      (node (ref "B1") (pin "DIAG0") (pinfunction "DIAG0_DIAG0") (pintype "bidirectional"))
    )
    (net (code "78") (name "unconnected-(B1-PadDIAG1)") (class "Default")
      (node (ref "B1") (pin "DIAG1") (pinfunction "DIAG1_DIAG1") (pintype "bidirectional"))
    )
    (net (code "79") (name "unconnected-(B1-PadVREF)") (class "Default")
      (node (ref "B1") (pin "VREF") (pinfunction "VREF_VREF") (pintype "passive"))
    )
    (net (code "80") (name "unconnected-(B2-PadDIAG0)") (class "Default")
      (node (ref "B2") (pin "DIAG0") (pinfunction "DIAG0_DIAG0") (pintype "bidirectional"))
    )
    (net (code "81") (name "unconnected-(B2-PadDIAG1)") (class "Default")
      (node (ref "B2") (pin "DIAG1") (pinfunction "DIAG1_DIAG1") (pintype "bidirectional"))
    )
    (net (code "82") (name "unconnected-(B2-PadVREF)") (class "Default")
      (node (ref "B2") (pin "VREF") (pinfunction "VREF_VREF") (pintype "passive"))
    )
    (net (code "83") (name "unconnected-(B3-PadDIAG0)") (class "Default")
      (node (ref "B3") (pin "DIAG0") (pinfunction "DIAG0_DIAG0") (pintype "bidirectional"))
    )
    (net (code "84") (name "unconnected-(B3-PadDIAG1)") (class "Default")
      (node (ref "B3") (pin "DIAG1") (pinfunction "DIAG1_DIAG1") (pintype "bidirectional"))
    )
    (net (code "85") (name "unconnected-(B3-PadVREF)") (class "Default")
      (node (ref "B3") (pin "VREF") (pinfunction "VREF_VREF") (pintype "passive"))
    )
    (net (code "86") (name "unconnected-(B4-PadDIAG0)") (class "Default")
      (node (ref "B4") (pin "DIAG0") (pinfunction "DIAG0_DIAG0") (pintype "bidirectional"))
    )
    (net (code "87") (name "unconnected-(B4-PadDIAG1)") (class "Default")
      (node (ref "B4") (pin "DIAG1") (pinfunction "DIAG1_DIAG1") (pintype "bidirectional"))
    )
    (net (code "88") (name "unconnected-(B4-PadVREF)") (class "Default")
      (node (ref "B4") (pin "VREF") (pinfunction "VREF_VREF") (pintype "passive"))
    )
    (net (code "89") (name "unconnected-(B5-PadDIAG0)") (class "Default")
      (node (ref "B5") (pin "DIAG0") (pinfunction "DIAG0_DIAG0") (pintype "bidirectional"))
    )
    (net (code "90") (name "unconnected-(B5-PadDIAG1)") (class "Default")
      (node (ref "B5") (pin "DIAG1") (pinfunction "DIAG1_DIAG1") (pintype "bidirectional"))
    )
    (net (code "91") (name "unconnected-(B5-PadVREF)") (class "Default")
      (node (ref "B5") (pin "VREF") (pinfunction "VREF_VREF") (pintype "passive"))
    )
    (net (code "92") (name "unconnected-(B6-PadDIAG0)") (class "Default")
      (node (ref "B6") (pin "DIAG0") (pinfunction "DIAG0_DIAG0") (pintype "bidirectional"))
    )
    (net (code "93") (name "unconnected-(B6-PadDIAG1)") (class "Default")
      (node (ref "B6") (pin "DIAG1") (pinfunction "DIAG1_DIAG1") (pintype "bidirectional"))
    )
    (net (code "94") (name "unconnected-(B6-PadVREF)") (class "Default")
      (node (ref "B6") (pin "VREF") (pinfunction "VREF_VREF") (pintype "passive"))
    )
    (net (code "95") (name "unconnected-(B7-PadDIAG0)") (class "Default")
      (node (ref "B7") (pin "DIAG0") (pinfunction "DIAG0_DIAG0") (pintype "bidirectional"))
    )
    (net (code "96") (name "unconnected-(B7-PadDIAG1)") (class "Default")
      (node (ref "B7") (pin "DIAG1") (pinfunction "DIAG1_DIAG1") (pintype "bidirectional"))
    )
    (net (code "97") (name "unconnected-(B7-PadVREF)") (class "Default")
      (node (ref "B7") (pin "VREF") (pinfunction "VREF_VREF") (pintype "passive"))
    )
    (net (code "98") (name "unconnected-(U$1-Pad0{slash}RX)") (class "Default")
      (node (ref "U$1") (pin "0/RX") (pinfunction "0/RX_0/RX") (pintype "bidirectional"))
    )
    (net (code "99") (name "unconnected-(U$1-Pad1{slash}TX)") (class "Default")
      (node (ref "U$1") (pin "1/TX") (pinfunction "1/TX_1/TX") (pintype "bidirectional"))
    )
    (net (code "100") (name "unconnected-(U$1-Pad3V3_2)") (class "Default")
      (node (ref "U$1") (pin "3V3_2") (pinfunction "3V3_2_3V3_2") (pintype "bidirectional"))
    )
    (net (code "101") (name "unconnected-(U$1-Pad3V3_LO)") (class "Default")
      (node (ref "U$1") (pin "3V3_LO") (pinfunction "3V3_LO_3V3_LO") (pintype "bidirectional"))
    )
    (net (code "102") (name "unconnected-(U$1-Pad10{slash}CS)") (class "Default")
      (node (ref "U$1") (pin "10/CS") (pinfunction "10/CS_10/CS") (pintype "bidirectional"))
    )
    (net (code "103") (name "unconnected-(U$1-Pad14{slash}A0)") (class "Default")
      (node (ref "U$1") (pin "14/A0") (pinfunction "14/A0_14/A0") (pintype "bidirectional"))
    )
    (net (code "104") (name "unconnected-(U$1-PadAGND)") (class "Default")
      (node (ref "U$1") (pin "AGND") (pinfunction "AGND_AGND") (pintype "bidirectional"))
    )
    (net (code "105") (name "unconnected-(U$1-PadPROG)") (class "Default")
      (node (ref "U$1") (pin "PROG") (pinfunction "PROG_PROG") (pintype "bidirectional"))
    )
    (net (code "106") (name "unconnected-(U$1-PadRESET)") (class "Default")
      (node (ref "U$1") (pin "RESET") (pinfunction "RESET_RESET") (pintype "bidirectional"))
    )
    (net (code "107") (name "unconnected-(U$1-PadU5V)") (class "Default")
      (node (ref "U$1") (pin "U5V") (pinfunction "U5V_U5V") (pintype "bidirectional"))
    )
    (net (code "108") (name "unconnected-(U$1-PadUD+)") (class "Default")
      (node (ref "U$1") (pin "UD+") (pinfunction "UD+_UD+") (pintype "bidirectional"))
    )
    (net (code "109") (name "unconnected-(U$1-PadUD-)") (class "Default")
      (node (ref "U$1") (pin "UD-") (pinfunction "UD-_UD-") (pintype "bidirectional"))
    )
    (net (code "110") (name "unconnected-(U$1-PadUGND1)") (class "Default")
      (node (ref "U$1") (pin "UGND1") (pinfunction "UGND1_UGND1") (pintype "bidirectional"))
    )
    (net (code "111") (name "unconnected-(U$1-PadUGND2)") (class "Default")
      (node (ref "U$1") (pin "UGND2") (pinfunction "UGND2_UGND2") (pintype "bidirectional"))
    )
    (net (code "112") (name "unconnected-(U$1-PadVBAT)") (class "Default")
      (node (ref "U$1") (pin "VBAT") (pinfunction "VBAT_VBAT") (pintype "bidirectional"))
    )
    (net (code "113") (name "unconnected-(U$1-PadVIN)") (class "Default")
      (node (ref "U$1") (pin "VIN") (pinfunction "VIN_VIN") (pintype "bidirectional"))
    )
    (net (code "114") (name "unconnected-(U$1-PadVUSB)") (class "Default")
      (node (ref "U$1") (pin "VUSB") (pinfunction "VUSB_VUSB") (pintype "bidirectional"))
    )
  )
)
